# Arduino.net
KiCad netlist of a schematic drawn in Altium Designer
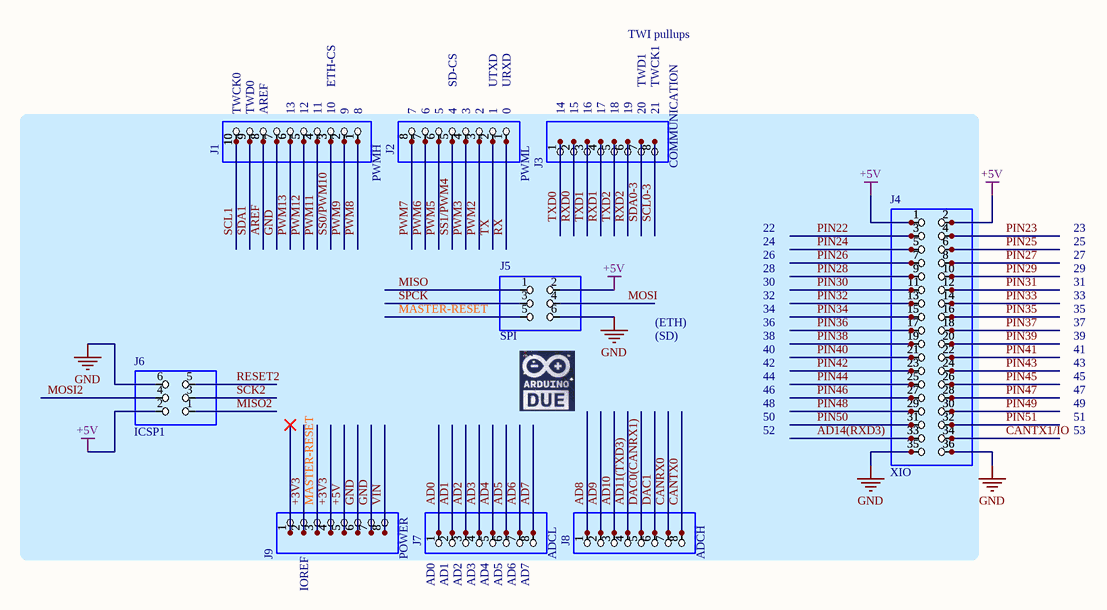
[diagram p0: Arduino.SchDoc]

(export (version "E")
  (design (tool "Eeschema 10.0.6"))
  (components
    (comp (ref "J1") (value "PWMH") (footprint "1X10") (libsource (lib "SmartPrj") (part "PINHD-1X10")))
    (comp (ref "J2") (value "PWML") (footprint "1X08") (libsource (lib "SmartPrj") (part "PINHD-1X8")))
    (comp (ref "J3")
      (value "COMMUNICATION")
      (footprint "1X08")
      (libsource (lib "SmartPrj") (part "PINHD-1X8"))
    )
    (comp (ref "J4") (value "XIO") (footprint "2X18") (libsource (lib "SmartPrj") (part "PINHD-2X18")))
    (comp (ref "J5") (value "SPI") (footprint "2X03") (libsource (lib "SmartPrj") (part "PINHD-2X3")))
    (comp (ref "J6") (value "ICSP1") (footprint "2X03") (libsource (lib "SmartPrj") (part "PINHD-2X3")))
    (comp (ref "J7") (value "ADCL") (footprint "1X08") (libsource (lib "SmartPrj") (part "PINHD-1X8")))
    (comp (ref "J8") (value "ADCH") (footprint "1X08") (libsource (lib "SmartPrj") (part "PINHD-1X8")))
    (comp (ref "J9") (value "POWER") (footprint "1X08") (libsource (lib "SmartPrj") (part "PINHD-1X8")))
  )
  (nets
    (net (code "1") (name "+5V") (class "Default")
      (node (ref "J4") (pin "1") (pinfunction "1_1") (pintype "passive"))
      (node (ref "J4") (pin "2") (pinfunction "2_2") (pintype "passive"))
      (node (ref "J5") (pin "2") (pinfunction "2_2") (pintype "passive"))
      (node (ref "J6") (pin "2") (pinfunction "2_2") (pintype "passive"))
      (node (ref "J9") (pin "5") (pinfunction "5_5") (pintype "passive"))
    )
    (net (code "2") (name "/+3V3") (class "Default")
      (node (ref "J9") (pin "2") (pinfunction "2_2") (pintype "passive"))
      (node (ref "J9") (pin "4") (pinfunction "4_4") (pintype "passive"))
    )
    (net (code "3") (name "/AD0") (class "Default")
      (node (ref "J7") (pin "1") (pinfunction "1_1") (pintype "passive"))
    )
    (net (code "4") (name "/AD1") (class "Default")
      (node (ref "J7") (pin "2") (pinfunction "2_2") (pintype "passive"))
    )
    (net (code "5") (name "/AD2") (class "Default")
      (node (ref "J7") (pin "3") (pinfunction "3_3") (pintype "passive"))
    )
    (net (code "6") (name "/AD3") (class "Default")
      (node (ref "J7") (pin "4") (pinfunction "4_4") (pintype "passive"))
    )
    (net (code "7") (name "/AD4") (class "Default")
      (node (ref "J7") (pin "5") (pinfunction "5_5") (pintype "passive"))
    )
    (net (code "8") (name "/AD5") (class "Default")
      (node (ref "J7") (pin "6") (pinfunction "6_6") (pintype "passive"))
    )
    (net (code "9") (name "/AD6") (class "Default")
      (node (ref "J7") (pin "7") (pinfunction "7_7") (pintype "passive"))
    )
    (net (code "10") (name "/AD7") (class "Default")
      (node (ref "J7") (pin "8") (pinfunction "8_8") (pintype "passive"))
    )
    (net (code "11") (name "/AD8") (class "Default")
      (node (ref "J8") (pin "1") (pinfunction "1_1") (pintype "passive"))
    )
    (net (code "12") (name "/AD9") (class "Default")
      (node (ref "J8") (pin "2") (pinfunction "2_2") (pintype "passive"))
    )
    (net (code "13") (name "/AD10") (class "Default")
      (node (ref "J8") (pin "3") (pinfunction "3_3") (pintype "passive"))
    )
    (net (code "14") (name "/AD11(TXD3)") (class "Default")
      (node (ref "J8") (pin "4") (pinfunction "4_4") (pintype "passive"))
    )
    (net (code "15") (name "/AD14(RXD3)") (class "Default")
      (node (ref "J4") (pin "33") (pinfunction "33_33") (pintype "passive"))
    )
    (net (code "16") (name "/AREF") (class "Default")
      (node (ref "J1") (pin "8") (pinfunction "8_8") (pintype "passive"))
    )
    (net (code "17") (name "/CANRX0") (class "Default")
      (node (ref "J8") (pin "7") (pinfunction "7_7") (pintype "passive"))
    )
    (net (code "18") (name "/CANTX0") (class "Default")
      (node (ref "J8") (pin "8") (pinfunction "8_8") (pintype "passive"))
    )
    (net (code "19") (name "/CANTX1{slash}IO") (class "Default")
      (node (ref "J4") (pin "34") (pinfunction "34_34") (pintype "passive"))
    )
    (net (code "20") (name "/DAC0(CANRX1)") (class "Default")
      (node (ref "J8") (pin "5") (pinfunction "5_5") (pintype "passive"))
    )
    (net (code "21") (name "/DAC1") (class "Default")
      (node (ref "J8") (pin "6") (pinfunction "6_6") (pintype "passive"))
    )
    (net (code "22") (name "/MASTER-RESET") (class "Default")
      (node (ref "J5") (pin "5") (pinfunction "5_5") (pintype "passive"))
      (node (ref "J9") (pin "3") (pinfunction "3_3") (pintype "passive"))
    )
    (net (code "23") (name "/MISO") (class "Default")
      (node (ref "J5") (pin "1") (pinfunction "1_1") (pintype "passive"))
    )
    (net (code "24") (name "/MISO2") (class "Default")
      (node (ref "J6") (pin "1") (pinfunction "1_1") (pintype "passive"))
    )
    (net (code "25") (name "/MOSI") (class "Default")
      (node (ref "J5") (pin "4") (pinfunction "4_4") (pintype "passive"))
    )
    (net (code "26") (name "/MOSI2") (class "Default")
      (node (ref "J6") (pin "4") (pinfunction "4_4") (pintype "passive"))
    )
    (net (code "27") (name "/PIN22") (class "Default")
      (node (ref "J4") (pin "3") (pinfunction "3_3") (pintype "passive"))
    )
    (net (code "28") (name "/PIN23") (class "Default")
      (node (ref "J4") (pin "4") (pinfunction "4_4") (pintype "passive"))
    )
    (net (code "29") (name "/PIN24") (class "Default")
      (node (ref "J4") (pin "5") (pinfunction "5_5") (pintype "passive"))
    )
    (net (code "30") (name "/PIN25") (class "Default")
      (node (ref "J4") (pin "6") (pinfunction "6_6") (pintype "passive"))
    )
    (net (code "31") (name "/PIN26") (class "Default")
      (node (ref "J4") (pin "7") (pinfunction "7_7") (pintype "passive"))
    )
    (net (code "32") (name "/PIN27") (class "Default")
      (node (ref "J4") (pin "8") (pinfunction "8_8") (pintype "passive"))
    )
    (net (code "33") (name "/PIN28") (class "Default")
      (node (ref "J4") (pin "9") (pinfunction "9_9") (pintype "passive"))
    )
    (net (code "34") (name "/PIN29") (class "Default")
      (node (ref "J4") (pin "10") (pinfunction "10_10") (pintype "passive"))
    )
    (net (code "35") (name "/PIN30") (class "Default")
      (node (ref "J4") (pin "11") (pinfunction "11_11") (pintype "passive"))
    )
    (net (code "36") (name "/PIN31") (class "Default")
      (node (ref "J4") (pin "12") (pinfunction "12_12") (pintype "passive"))
    )
    (net (code "37") (name "/PIN32") (class "Default")
      (node (ref "J4") (pin "13") (pinfunction "13_13") (pintype "passive"))
    )
    (net (code "38") (name "/PIN33") (class "Default")
      (node (ref "J4") (pin "14") (pinfunction "14_14") (pintype "passive"))
    )
    (net (code "39") (name "/PIN34") (class "Default")
      (node (ref "J4") (pin "15") (pinfunction "15_15") (pintype "passive"))
    )
    (net (code "40") (name "/PIN35") (class "Default")
      (node (ref "J4") (pin "16") (pinfunction "16_16") (pintype "passive"))
    )
    (net (code "41") (name "/PIN36") (class "Default")
      (node (ref "J4") (pin "17") (pinfunction "17_17") (pintype "passive"))
    )
    (net (code "42") (name "/PIN37") (class "Default")
      (node (ref "J4") (pin "18") (pinfunction "18_18") (pintype "passive"))
    )
    (net (code "43") (name "/PIN38") (class "Default")
      (node (ref "J4") (pin "19") (pinfunction "19_19") (pintype "passive"))
    )
    (net (code "44") (name "/PIN39") (class "Default")
      (node (ref "J4") (pin "20") (pinfunction "20_20") (pintype "passive"))
    )
    (net (code "45") (name "/PIN40") (class "Default")
      (node (ref "J4") (pin "21") (pinfunction "21_21") (pintype "passive"))
    )
    (net (code "46") (name "/PIN41") (class "Default")
      (node (ref "J4") (pin "22") (pinfunction "22_22") (pintype "passive"))
    )
    (net (code "47") (name "/PIN42") (class "Default")
      (node (ref "J4") (pin "23") (pinfunction "23_23") (pintype "passive"))
    )
    (net (code "48") (name "/PIN43") (class "Default")
      (node (ref "J4") (pin "24") (pinfunction "24_24") (pintype "passive"))
    )
    (net (code "49") (name "/PIN44") (class "Default")
      (node (ref "J4") (pin "25") (pinfunction "25_25") (pintype "passive"))
    )
    (net (code "50") (name "/PIN45") (class "Default")
      (node (ref "J4") (pin "26") (pinfunction "26_26") (pintype "passive"))
    )
    (net (code "51") (name "/PIN46") (class "Default")
      (node (ref "J4") (pin "27") (pinfunction "27_27") (pintype "passive"))
    )
    (net (code "52") (name "/PIN47") (class "Default")
      (node (ref "J4") (pin "28") (pinfunction "28_28") (pintype "passive"))
    )
    (net (code "53") (name "/PIN48") (class "Default")
      (node (ref "J4") (pin "29") (pinfunction "29_29") (pintype "passive"))
    )
    (net (code "54") (name "/PIN49") (class "Default")
      (node (ref "J4") (pin "30") (pinfunction "30_30") (pintype "passive"))
    )
    (net (code "55") (name "/PIN50") (class "Default")
      (node (ref "J4") (pin "31") (pinfunction "31_31") (pintype "passive"))
    )
    (net (code "56") (name "/PIN51") (class "Default")
      (node (ref "J4") (pin "32") (pinfunction "32_32") (pintype "passive"))
    )
    (net (code "57") (name "/PWM2") (class "Default")
      (node (ref "J2") (pin "3") (pinfunction "3_3") (pintype "passive"))
    )
    (net (code "58") (name "/PWM3") (class "Default")
      (node (ref "J2") (pin "4") (pinfunction "4_4") (pintype "passive"))
    )
    (net (code "59") (name "/PWM5") (class "Default")
      (node (ref "J2") (pin "6") (pinfunction "6_6") (pintype "passive"))
    )
    (net (code "60") (name "/PWM6") (class "Default")
      (node (ref "J2") (pin "7") (pinfunction "7_7") (pintype "passive"))
    )
    (net (code "61") (name "/PWM7") (class "Default")
      (node (ref "J2") (pin "8") (pinfunction "8_8") (pintype "passive"))
    )
    (net (code "62") (name "/PWM8") (class "Default")
      (node (ref "J1") (pin "1") (pinfunction "1_1") (pintype "passive"))
    )
    (net (code "63") (name "/PWM9") (class "Default")
      (node (ref "J1") (pin "2") (pinfunction "2_2") (pintype "passive"))
    )
    (net (code "64") (name "/PWM11") (class "Default")
      (node (ref "J1") (pin "4") (pinfunction "4_4") (pintype "passive"))
    )
    (net (code "65") (name "/PWM12") (class "Default")
      (node (ref "J1") (pin "5") (pinfunction "5_5") (pintype "passive"))
    )
    (net (code "66") (name "/PWM13") (class "Default")
      (node (ref "J1") (pin "6") (pinfunction "6_6") (pintype "passive"))
    )
    (net (code "67") (name "/RESET2") (class "Default")
      (node (ref "J6") (pin "5") (pinfunction "5_5") (pintype "passive"))
    )
    (net (code "68") (name "/RX") (class "Default")
      (node (ref "J2") (pin "1") (pinfunction "1_1") (pintype "passive"))
    )
    (net (code "69") (name "/RXD0") (class "Default")
      (node (ref "J3") (pin "2") (pinfunction "2_2") (pintype "passive"))
    )
    (net (code "70") (name "/RXD1") (class "Default")
      (node (ref "J3") (pin "4") (pinfunction "4_4") (pintype "passive"))
    )
    (net (code "71") (name "/RXD2") (class "Default")
      (node (ref "J3") (pin "6") (pinfunction "6_6") (pintype "passive"))
    )
    (net (code "72") (name "/SCK2") (class "Default")
      (node (ref "J6") (pin "3") (pinfunction "3_3") (pintype "passive"))
    )
    (net (code "73") (name "/SCL0-3") (class "Default")
      (node (ref "J3") (pin "8") (pinfunction "8_8") (pintype "passive"))
    )
    (net (code "74") (name "/SCL1") (class "Default")
      (node (ref "J1") (pin "10") (pinfunction "10_10") (pintype "passive"))
    )
    (net (code "75") (name "/SDA0-3") (class "Default")
      (node (ref "J3") (pin "7") (pinfunction "7_7") (pintype "passive"))
    )
    (net (code "76") (name "/SDA1") (class "Default")
      (node (ref "J1") (pin "9") (pinfunction "9_9") (pintype "passive"))
    )
    (net (code "77") (name "/SPCK") (class "Default")
      (node (ref "J5") (pin "3") (pinfunction "3_3") (pintype "passive"))
    )
    (net (code "78") (name "/SS0{slash}PWM10") (class "Default")
      (node (ref "J1") (pin "3") (pinfunction "3_3") (pintype "passive"))
    )
    (net (code "79") (name "/SS1{slash}PWM4") (class "Default")
      (node (ref "J2") (pin "5") (pinfunction "5_5") (pintype "passive"))
    )
    (net (code "80") (name "/TX") (class "Default")
      (node (ref "J2") (pin "2") (pinfunction "2_2") (pintype "passive"))
    )
    (net (code "81") (name "/TXD0") (class "Default")
      (node (ref "J3") (pin "1") (pinfunction "1_1") (pintype "passive"))
    )
    (net (code "82") (name "/TXD1") (class "Default")
      (node (ref "J3") (pin "3") (pinfunction "3_3") (pintype "passive"))
    )
    (net (code "83") (name "/TXD2") (class "Default")
      (node (ref "J3") (pin "5") (pinfunction "5_5") (pintype "passive"))
    )
    (net (code "84") (name "/VIN") (class "Default")
      (node (ref "J9") (pin "8") (pinfunction "8_8") (pintype "passive"))
    )
    (net (code "85") (name "GND") (class "Default")
      (node (ref "J1") (pin "7") (pinfunction "7_7") (pintype "passive"))
      (node (ref "J4") (pin "35") (pinfunction "35_35") (pintype "passive"))
      (node (ref "J4") (pin "36") (pinfunction "36_36") (pintype "passive"))
      (node (ref "J5") (pin "6") (pinfunction "6_6") (pintype "passive"))
      (node (ref "J6") (pin "6") (pinfunction "6_6") (pintype "passive"))
      (node (ref "J9") (pin "6") (pinfunction "6_6") (pintype "passive"))
      (node (ref "J9") (pin "7") (pinfunction "7_7") (pintype "passive"))
    )
    (net (code "86") (name "unconnected-(J9-Pad1)") (class "Default")
      (node (ref "J9") (pin "1") (pinfunction "1_1") (pintype "passive+no_connect"))
    )
  )
)
